# EDAv0_1.net
KiCad netlist of a schematic drawn in EasyEDA Pro
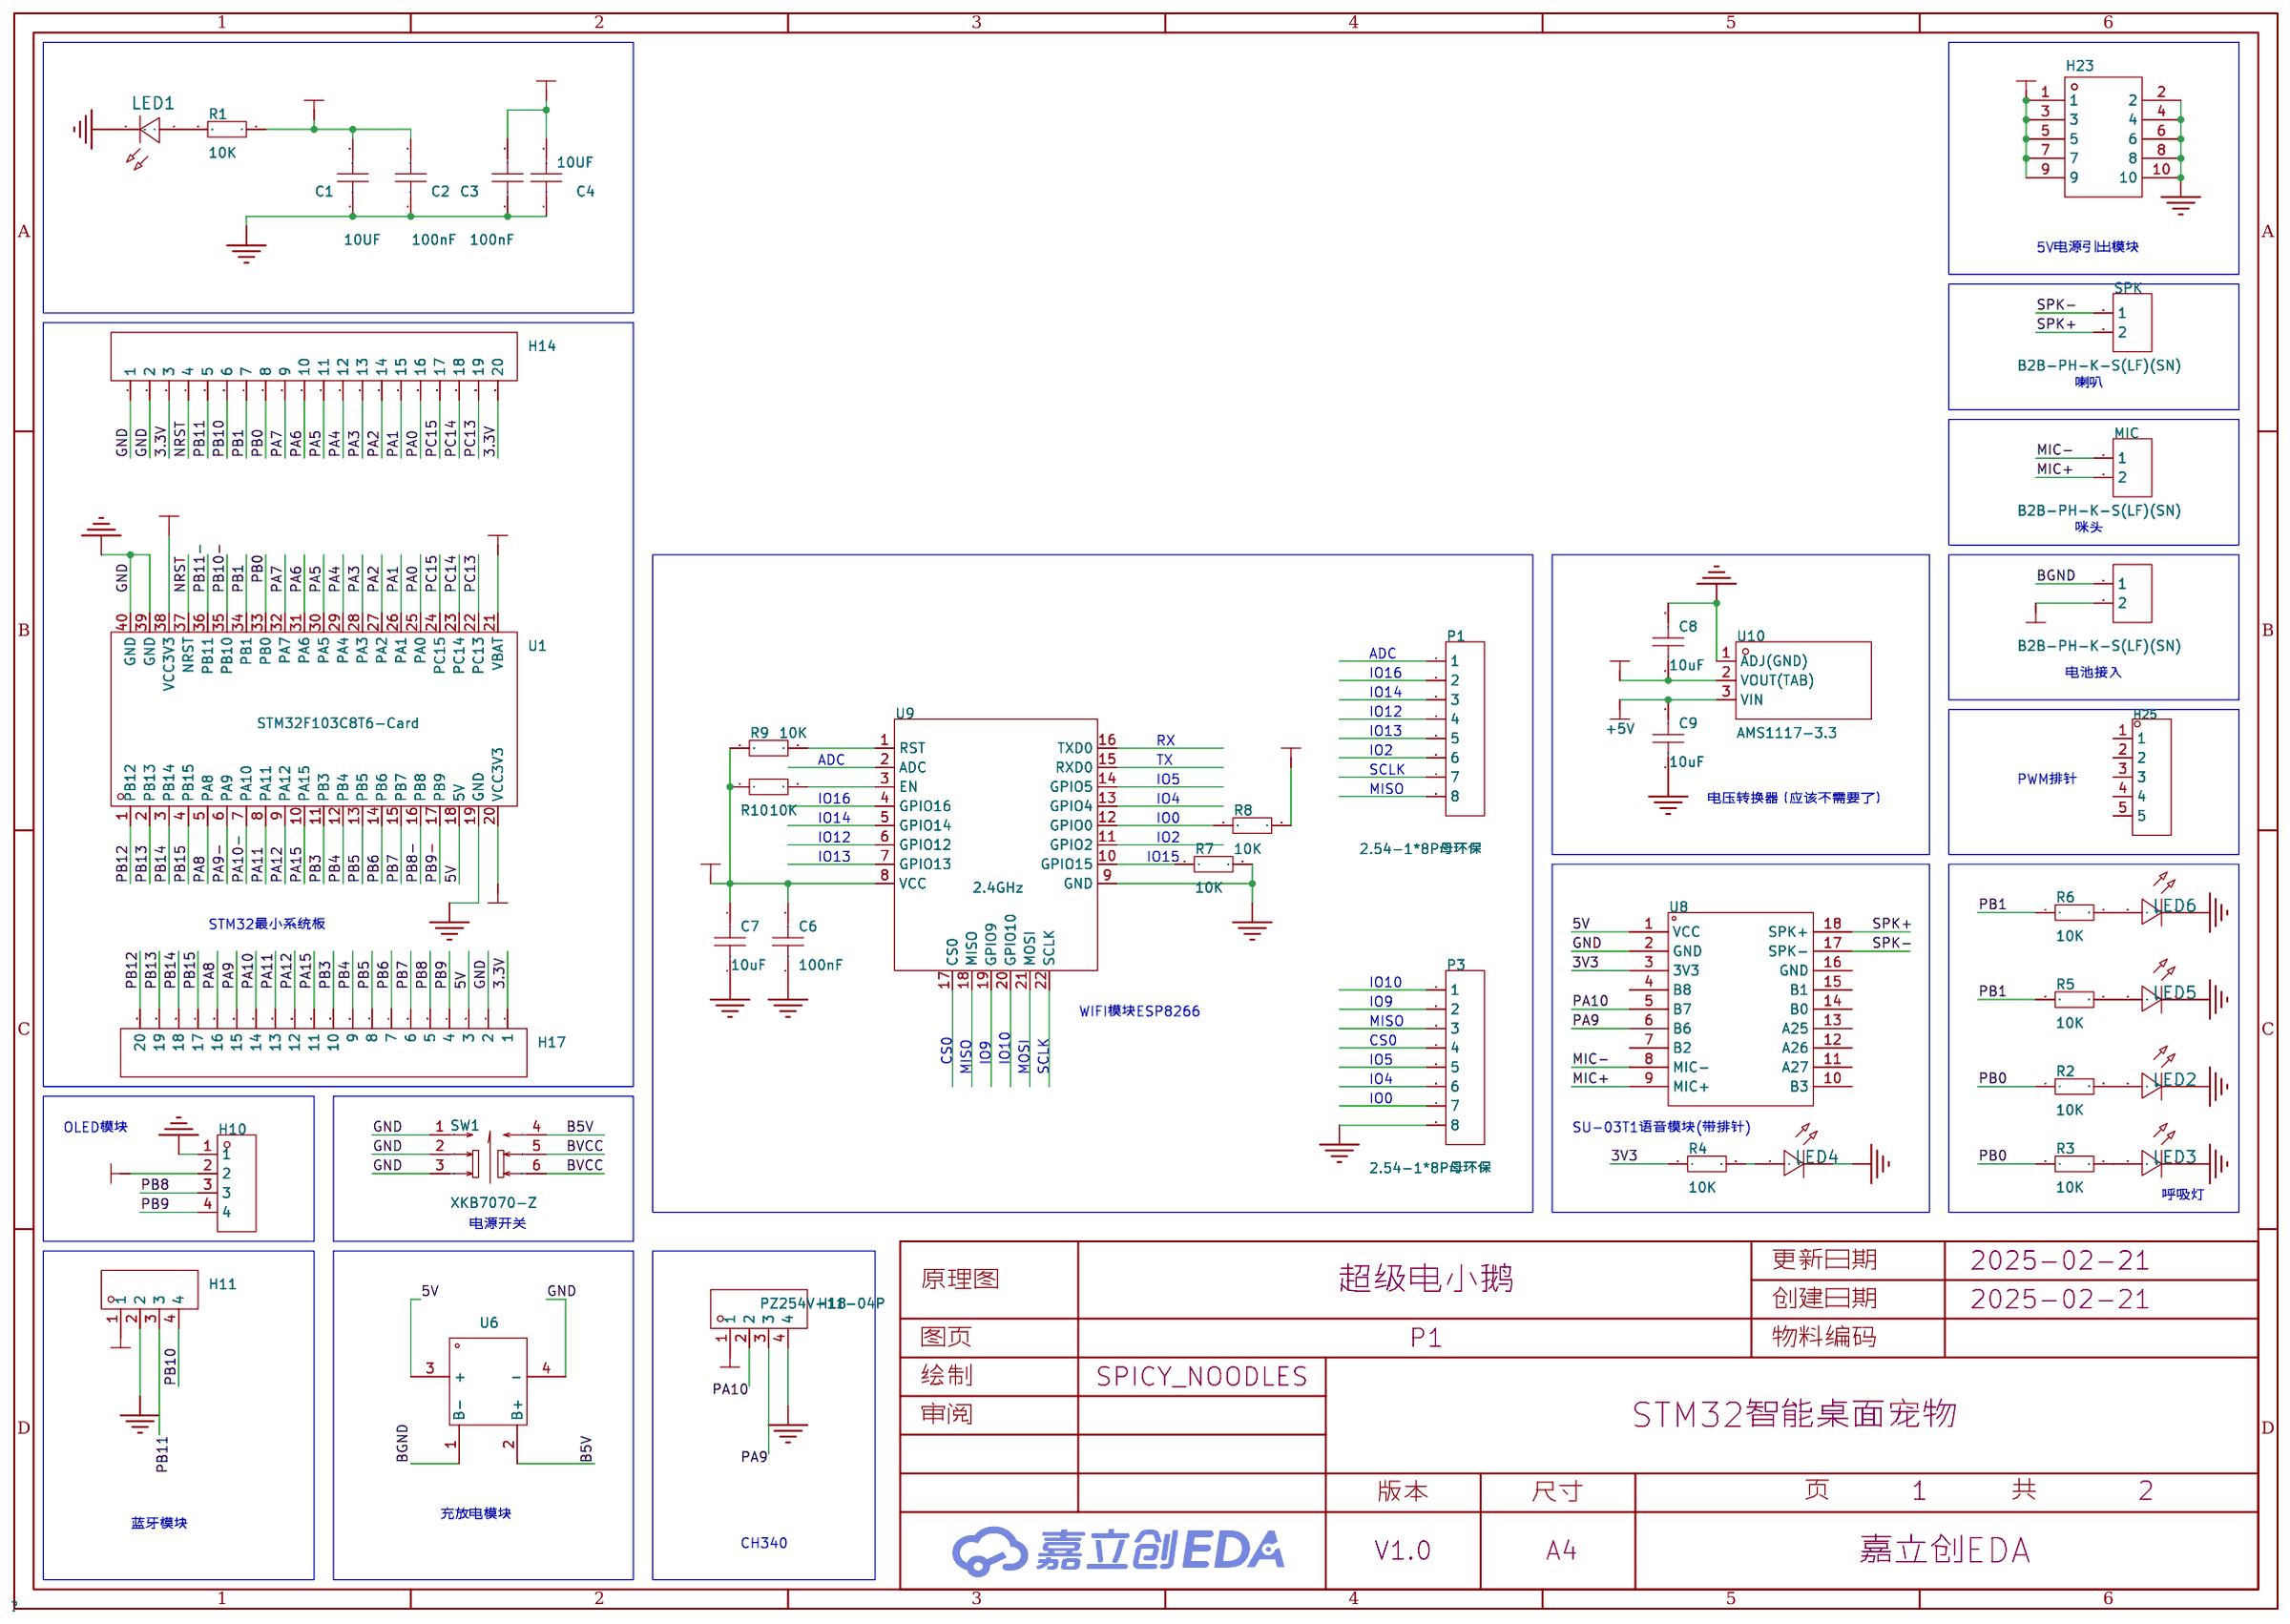
[diagram p0: schematic sheet]

(export (version "E")
  (design (tool "Eeschema 10.0.6"))
  (components
    (comp (ref "Battery")
      (value "B2B-PH-K-S(LF)(SN)")
      (footprint "easyedapro:HDR-TH_2P-P2.54-V-F")
      (fields (field (name "Manufacturer") "JST"))
      (libsource (lib "easyedapro") (part "Header-Female-2.54_1x2"))
    )
    (comp (ref "C1")
      (value "10UF")
      (footprint "easyedapro:C0805")
      (libsource (lib "easyedapro") (part "CapAcitance"))
    )
    (comp (ref "C2")
      (value "100nF")
      (footprint "easyedapro:C0805")
      (libsource (lib "easyedapro") (part "CapAcitance"))
    )
    (comp (ref "C3")
      (value "100nF")
      (footprint "easyedapro:C0805")
      (libsource (lib "easyedapro") (part "CapAcitance"))
    )
    (comp (ref "C4")
      (value "10UF")
      (footprint "easyedapro:C0805")
      (libsource (lib "easyedapro") (part "CapAcitance"))
    )
    (comp (ref "C6")
      (value "100nF")
      (footprint "easyedapro:C0805")
      (libsource (lib "easyedapro") (part "CapAcitance"))
    )
    (comp (ref "C7")
      (value "10uF")
      (footprint "easyedapro:C0603")
      (description "容值:10uF;精度:±10%;额定电压:10V;材质(温度系数):X5R;")
      (fields
        (field (name "Manufacturer Part") "CGA0603X5R106K100JT")
        (field (name "Manufacturer") "HRE(芯声)")
      )
      (libsource (lib "easyedapro") (part "CGA0603X5R106K100JT"))
    )
    (comp (ref "C8")
      (value "10uF")
      (footprint "easyedapro:C0603")
      (description "容值:10uF;精度:±10%;额定电压:10V;材质(温度系数):X5R;")
      (fields
        (field (name "Manufacturer Part") "CGA0603X5R106K100JT")
        (field (name "Manufacturer") "HRE(芯声)")
      )
      (libsource (lib "easyedapro") (part "CGA0603X5R106K100JT"))
    )
    (comp (ref "C9")
      (value "10uF")
      (footprint "easyedapro:C0603")
      (description "容值:10uF;精度:±10%;额定电压:10V;材质(温度系数):X5R;")
      (fields
        (field (name "Manufacturer Part") "CGA0603X5R106K100JT")
        (field (name "Manufacturer") "HRE(芯声)")
      )
      (libsource (lib "easyedapro") (part "CGA0603X5R106K100JT"))
    )
    (comp (ref "H10")
      (value "~")
      (footprint "easyedapro:HDR-TH_4P-P2.54-V-F")
      (libsource (lib "easyedapro") (part "2.54-1*4P母"))
    )
    (comp (ref "H11")
      (value "~")
      (footprint "easyedapro:HDR-TH_4P-P2.54-V-F")
      (libsource (lib "easyedapro") (part "2.54-1*4P母"))
    )
    (comp (ref "H14")
      (value "~")
      (footprint "easyedapro:HDR-TH_20P-P2.54-V-F")
      (libsource (lib "easyedapro") (part "HDR-F_2.54_1x20P"))
    )
    (comp (ref "H17")
      (value "~")
      (footprint "easyedapro:HDR-TH_20P-P2.54-V-F")
      (libsource (lib "easyedapro") (part "HDR-F_2.54_1x20P"))
    )
    (comp (ref "H18")
      (value "PZ254V-11-04P")
      (footprint "easyedapro:HDR-TH_4P-P2.54-V-F")
      (fields (field (name "Manufacturer") "XFCN(兴飞)"))
      (libsource (lib "easyedapro") (part "2.54-1*4P母"))
    )
    (comp (ref "H23")
      (value "~")
      (footprint "easyedapro:HDR-TH_10P-P2.54-V-M-R2-C5-S2.54")
      (libsource (lib "easyedapro") (part "HDR-M-2.54_2x5"))
    )
    (comp (ref "H25")
      (value "~")
      (footprint "easyedapro:HDR-TH_5P-P2.54-V-M")
      (libsource (lib "easyedapro") (part "MTP125-1105S1"))
    )
    (comp (ref "LED1")
      (value "~")
      (footprint "easyedapro:LED_0805")
      (libsource (lib "easyedapro") (part "LED_R"))
    )
    (comp (ref "LED2")
      (value "~")
      (footprint "easyedapro:LED_0805")
      (libsource (lib "easyedapro") (part "LED_R"))
    )
    (comp (ref "LED3")
      (value "~")
      (footprint "easyedapro:LED_0805")
      (libsource (lib "easyedapro") (part "LED_R"))
    )
    (comp (ref "LED4")
      (value "~")
      (footprint "easyedapro:LED_0805")
      (libsource (lib "easyedapro") (part "LED_R"))
    )
    (comp (ref "LED5")
      (value "~")
      (footprint "easyedapro:LED_0805")
      (libsource (lib "easyedapro") (part "LED_R"))
    )
    (comp (ref "LED6")
      (value "~")
      (footprint "easyedapro:LED_0805")
      (libsource (lib "easyedapro") (part "LED_R"))
    )
    (comp (ref "MIC")
      (value "B2B-PH-K-S(LF)(SN)")
      (footprint "easyedapro:HDR-TH_2P-P2.54-V-F")
      (fields (field (name "Manufacturer") "JST"))
      (libsource (lib "easyedapro") (part "Header-Female-2.54_1x2"))
    )
    (comp (ref "P1")
      (value "2.54-1*8P母环保")
      (footprint "easyedapro:HDR-TH_8P-P2.54-V-F-1")
      (description "插孔结构:1x8P;间距:2.54mm;行距:-;安装类型:直插;排数:单排;总孔位数:8P;塑高:-;触头材质:-;触头镀层:-;")
      (fields (field (name "Manufacturer") "BOOMELE(博穆精密)"))
      (libsource (lib "easyedapro") (part "Header-Female-2.54_1x8"))
    )
    (comp (ref "P3")
      (value "2.54-1*8P母环保")
      (footprint "easyedapro:HDR-TH_8P-P2.54-V-F-1")
      (description "插孔结构:1x8P;间距:2.54mm;行距:-;安装类型:直插;排数:单排;总孔位数:8P;塑高:-;触头材质:-;触头镀层:-;")
      (fields (field (name "Manufacturer") "BOOMELE(博穆精密)"))
      (libsource (lib "easyedapro") (part "Header-Female-2.54_1x8"))
    )
    (comp (ref "R1") (value "10K") (footprint "easyedapro:R0805") (libsource (lib "easyedapro") (part "电阻")))
    (comp (ref "R2") (value "10K") (footprint "easyedapro:R0805") (libsource (lib "easyedapro") (part "电阻")))
    (comp (ref "R3") (value "10K") (footprint "easyedapro:R0805") (libsource (lib "easyedapro") (part "电阻")))
    (comp (ref "R4") (value "10K") (footprint "easyedapro:R0805") (libsource (lib "easyedapro") (part "电阻")))
    (comp (ref "R5") (value "10K") (footprint "easyedapro:R0805") (libsource (lib "easyedapro") (part "电阻")))
    (comp (ref "R6") (value "10K") (footprint "easyedapro:R0805") (libsource (lib "easyedapro") (part "电阻")))
    (comp (ref "R7") (value "10K") (footprint "easyedapro:R0805") (libsource (lib "easyedapro") (part "电阻")))
    (comp (ref "R8") (value "10K") (footprint "easyedapro:R0805") (libsource (lib "easyedapro") (part "电阻")))
    (comp (ref "R9") (value "10K") (footprint "easyedapro:R0805") (libsource (lib "easyedapro") (part "电阻")))
    (comp (ref "R10") (value "10K") (footprint "easyedapro:R0805") (libsource (lib "easyedapro") (part "电阻")))
    (comp (ref "SPK")
      (value "B2B-PH-K-S(LF)(SN)")
      (footprint "easyedapro:HDR-TH_2P-P2.54-V-F")
      (fields (field (name "Manufacturer") "JST"))
      (libsource (lib "easyedapro") (part "Header-Female-2.54_1x2"))
    )
    (comp (ref "SW1")
      (value "XKB7070-Z")
      (footprint "easyedapro:SW-TH_6P-L7.0-W7.0-P2.00")
      (description "自锁/无锁:自锁;安装方式:直插;触点电流:100mA;额定电压 (AC):250V;额定电压 (DC):30V;带灯:不带;作用力:160gf;机械寿命:10万次;")
      (fields (field (name "Manufacturer") "XKB Connectivity(中国星坤)"))
      (libsource (lib "easyedapro") (part "XKB7070-Z"))
    )
    (comp (ref "U1")
      (value "STM32F103C8T6-Card")
      (footprint "easyedapro:CONN-TH_L53.3-W22.9_STM32F103C8T6-CARD")
      (libsource (lib "easyedapro") (part "STM32F103C8T6-CARD"))
    )
    (comp (ref "U6") (value "~") (libsource (lib "easyedapro") (part "5V充放电模块")))
    (comp (ref "U8")
      (value "~")
      (footprint "easyedapro:SU-03T带排针")
      (libsource (lib "easyedapro") (part "SU-03T带排针"))
    )
    (comp (ref "U9")
      (value "2.4GHz")
      (footprint "easyedapro:WIFIM-SMD_ESP-12F-ESP8266MOD")
      (description "核心处理器:ESP8266芯片;频率:2.4GHz;天线形式:板载PCB天线;发射功率:16dBm;接收灵敏度:-90dBm;")
      (fields
        (field (name "Manufacturer Part") "ESP-12F(ESP8266MOD)")
        (field (name "Manufacturer") "Ai-Thinker(安信可)")
      )
      (libsource (lib "easyedapro") (part "ESP-12F(ESP8266MOD)"))
    )
    (comp (ref "U10")
      (value "AMS1117-3.3")
      (footprint "easyedapro:SOT-89_L4.5-W2.5-P1.50-LS4.2-BR")
      (description "输出类型:固定;工作电压:18V;输出电压:3.3V;输出电流:1A;电源纹波抑制比(PSRR):60dB@(120Hz);输出极性:正极;")
      (fields (field (name "Manufacturer") "UMW(友台半导体)"))
      (libsource (lib "easyedapro") (part "AMS1117-3.3_C347256"))
    )
  )
  (nets
    (net (code "1") (name "+5V") (class "Default")
      (node (ref "C9") (pin "2") (pinfunction "2_2") (pintype "unspecified"))
      (node (ref "U10") (pin "3") (pinfunction "VIN_3") (pintype "unspecified"))
    )
    (net (code "2") (name "/3V3") (class "Default")
      (node (ref "R4") (pin "1") (pinfunction "1_1") (pintype "input"))
      (node (ref "U8") (pin "3") (pinfunction "3V3_3") (pintype "input"))
    )
    (net (code "3") (name "/B5V") (class "Default")
      (node (ref "SW1") (pin "4") (pinfunction "4_4") (pintype "unspecified"))
      (node (ref "U6") (pin "2") (pinfunction "B+_2") (pintype "input"))
    )
    (net (code "4") (name "/BGND") (class "Default")
      (node (ref "Battery") (pin "1") (pinfunction "1_1") (pintype "input"))
      (node (ref "U6") (pin "1") (pinfunction "B-_1") (pintype "input"))
    )
    (net (code "5") (name "/MIC+") (class "Default")
      (node (ref "MIC") (pin "2") (pinfunction "2_2") (pintype "input"))
      (node (ref "U8") (pin "9") (pinfunction "MIC+_9") (pintype "input"))
    )
    (net (code "6") (name "/MIC-") (class "Default")
      (node (ref "MIC") (pin "1") (pinfunction "1_1") (pintype "input"))
      (node (ref "U8") (pin "8") (pinfunction "MIC-_8") (pintype "input"))
    )
    (net (code "7") (name "/NRST") (class "Default")
      (node (ref "H14") (pin "4") (pinfunction "4_4") (pintype "input"))
      (node (ref "U1") (pin "37") (pinfunction "NRST_37") (pintype "unspecified"))
    )
    (net (code "8") (name "/PA0") (class "Default")
      (node (ref "H14") (pin "16") (pinfunction "16_16") (pintype "input"))
      (node (ref "U1") (pin "25") (pinfunction "PA0_25") (pintype "unspecified"))
    )
    (net (code "9") (name "/PA1") (class "Default")
      (node (ref "H14") (pin "15") (pinfunction "15_15") (pintype "input"))
      (node (ref "U1") (pin "26") (pinfunction "PA1_26") (pintype "unspecified"))
    )
    (net (code "10") (name "/PA2") (class "Default")
      (node (ref "H14") (pin "14") (pinfunction "14_14") (pintype "input"))
      (node (ref "U1") (pin "27") (pinfunction "PA2_27") (pintype "unspecified"))
    )
    (net (code "11") (name "/PA3") (class "Default")
      (node (ref "H14") (pin "13") (pinfunction "13_13") (pintype "input"))
      (node (ref "U1") (pin "28") (pinfunction "PA3_28") (pintype "unspecified"))
    )
    (net (code "12") (name "/PA4") (class "Default")
      (node (ref "H14") (pin "12") (pinfunction "12_12") (pintype "input"))
      (node (ref "U1") (pin "29") (pinfunction "PA4_29") (pintype "unspecified"))
    )
    (net (code "13") (name "/PA5") (class "Default")
      (node (ref "H14") (pin "11") (pinfunction "11_11") (pintype "input"))
      (node (ref "U1") (pin "30") (pinfunction "PA5_30") (pintype "unspecified"))
    )
    (net (code "14") (name "/PA6") (class "Default")
      (node (ref "H14") (pin "10") (pinfunction "10_10") (pintype "input"))
      (node (ref "U1") (pin "31") (pinfunction "PA6_31") (pintype "unspecified"))
    )
    (net (code "15") (name "/PA7") (class "Default")
      (node (ref "H14") (pin "9") (pinfunction "9_9") (pintype "input"))
      (node (ref "U1") (pin "32") (pinfunction "PA7_32") (pintype "unspecified"))
    )
    (net (code "16") (name "/PA8") (class "Default")
      (node (ref "H17") (pin "16") (pinfunction "16_16") (pintype "input"))
      (node (ref "U1") (pin "5") (pinfunction "PA8_5") (pintype "unspecified"))
    )
    (net (code "17") (name "/PA9") (class "Default")
      (node (ref "H17") (pin "15") (pinfunction "15_15") (pintype "input"))
      (node (ref "H18") (pin "3") (pinfunction "3_3") (pintype "unspecified"))
      (node (ref "U8") (pin "6") (pinfunction "B6_6") (pintype "input"))
    )
    (net (code "18") (name "/PA9-") (class "Default")
      (node (ref "U1") (pin "6") (pinfunction "PA9_6") (pintype "unspecified"))
    )
    (net (code "19") (name "/PA10") (class "Default")
      (node (ref "H17") (pin "14") (pinfunction "14_14") (pintype "input"))
      (node (ref "H18") (pin "2") (pinfunction "2_2") (pintype "unspecified"))
      (node (ref "U8") (pin "5") (pinfunction "B7_5") (pintype "input"))
    )
    (net (code "20") (name "/PA10-") (class "Default")
      (node (ref "U1") (pin "7") (pinfunction "PA10_7") (pintype "unspecified"))
    )
    (net (code "21") (name "/PA11") (class "Default")
      (node (ref "H17") (pin "13") (pinfunction "13_13") (pintype "input"))
      (node (ref "U1") (pin "8") (pinfunction "PA11_8") (pintype "unspecified"))
    )
    (net (code "22") (name "/PA12") (class "Default")
      (node (ref "H17") (pin "12") (pinfunction "12_12") (pintype "input"))
      (node (ref "U1") (pin "9") (pinfunction "PA12_9") (pintype "unspecified"))
    )
    (net (code "23") (name "/PA15") (class "Default")
      (node (ref "H17") (pin "11") (pinfunction "11_11") (pintype "input"))
      (node (ref "U1") (pin "10") (pinfunction "PA15_10") (pintype "unspecified"))
    )
    (net (code "24") (name "/PB0") (class "Default")
      (node (ref "H14") (pin "8") (pinfunction "8_8") (pintype "input"))
      (node (ref "R2") (pin "1") (pinfunction "1_1") (pintype "input"))
      (node (ref "R3") (pin "1") (pinfunction "1_1") (pintype "input"))
      (node (ref "U1") (pin "33") (pinfunction "PB0_33") (pintype "unspecified"))
    )
    (net (code "25") (name "/PB1") (class "Default")
      (node (ref "H14") (pin "7") (pinfunction "7_7") (pintype "input"))
      (node (ref "R5") (pin "1") (pinfunction "1_1") (pintype "input"))
      (node (ref "R6") (pin "1") (pinfunction "1_1") (pintype "input"))
      (node (ref "U1") (pin "34") (pinfunction "PB1_34") (pintype "unspecified"))
    )
    (net (code "26") (name "/PB3") (class "Default")
      (node (ref "H17") (pin "10") (pinfunction "10_10") (pintype "input"))
      (node (ref "U1") (pin "11") (pinfunction "PB3_11") (pintype "unspecified"))
    )
    (net (code "27") (name "/PB4") (class "Default")
      (node (ref "H17") (pin "9") (pinfunction "9_9") (pintype "input"))
      (node (ref "U1") (pin "12") (pinfunction "PB4_12") (pintype "unspecified"))
    )
    (net (code "28") (name "/PB5") (class "Default")
      (node (ref "H17") (pin "8") (pinfunction "8_8") (pintype "input"))
      (node (ref "U1") (pin "13") (pinfunction "PB5_13") (pintype "unspecified"))
    )
    (net (code "29") (name "/PB6") (class "Default")
      (node (ref "H17") (pin "7") (pinfunction "7_7") (pintype "input"))
      (node (ref "U1") (pin "14") (pinfunction "PB6_14") (pintype "unspecified"))
    )
    (net (code "30") (name "/PB7") (class "Default")
      (node (ref "H17") (pin "6") (pinfunction "6_6") (pintype "input"))
      (node (ref "U1") (pin "15") (pinfunction "PB7_15") (pintype "unspecified"))
    )
    (net (code "31") (name "/PB8") (class "Default")
      (node (ref "H10") (pin "3") (pinfunction "3_3") (pintype "unspecified"))
      (node (ref "H17") (pin "5") (pinfunction "5_5") (pintype "input"))
    )
    (net (code "32") (name "/PB8-") (class "Default")
      (node (ref "U1") (pin "16") (pinfunction "PB8_16") (pintype "unspecified"))
    )
    (net (code "33") (name "/PB9") (class "Default")
      (node (ref "H10") (pin "4") (pinfunction "4_4") (pintype "unspecified"))
      (node (ref "H17") (pin "4") (pinfunction "4_4") (pintype "input"))
    )
    (net (code "34") (name "/PB9-") (class "Default")
      (node (ref "U1") (pin "17") (pinfunction "PB9_17") (pintype "unspecified"))
    )
    (net (code "35") (name "/PB10") (class "Default")
      (node (ref "H11") (pin "4") (pinfunction "4_4") (pintype "unspecified"))
      (node (ref "H14") (pin "6") (pinfunction "6_6") (pintype "input"))
    )
    (net (code "36") (name "/PB10-") (class "Default")
      (node (ref "U1") (pin "35") (pinfunction "PB10_35") (pintype "unspecified"))
    )
    (net (code "37") (name "/PB11") (class "Default")
      (node (ref "H11") (pin "3") (pinfunction "3_3") (pintype "unspecified"))
      (node (ref "H14") (pin "5") (pinfunction "5_5") (pintype "input"))
    )
    (net (code "38") (name "/PB11-") (class "Default")
      (node (ref "U1") (pin "36") (pinfunction "PB11_36") (pintype "unspecified"))
    )
    (net (code "39") (name "/PB12") (class "Default")
      (node (ref "H17") (pin "20") (pinfunction "20_20") (pintype "input"))
      (node (ref "U1") (pin "1") (pinfunction "PB12_1") (pintype "unspecified"))
    )
    (net (code "40") (name "/PB13") (class "Default")
      (node (ref "H17") (pin "19") (pinfunction "19_19") (pintype "input"))
      (node (ref "U1") (pin "2") (pinfunction "PB13_2") (pintype "unspecified"))
    )
    (net (code "41") (name "/PB14") (class "Default")
      (node (ref "H17") (pin "18") (pinfunction "18_18") (pintype "input"))
      (node (ref "U1") (pin "3") (pinfunction "PB14_3") (pintype "unspecified"))
    )
    (net (code "42") (name "/PB15") (class "Default")
      (node (ref "H17") (pin "17") (pinfunction "17_17") (pintype "input"))
      (node (ref "U1") (pin "4") (pinfunction "PB15_4") (pintype "unspecified"))
    )
    (net (code "43") (name "/PC13") (class "Default")
      (node (ref "H14") (pin "19") (pinfunction "19_19") (pintype "input"))
      (node (ref "U1") (pin "22") (pinfunction "PC13_22") (pintype "unspecified"))
    )
    (net (code "44") (name "/PC14") (class "Default")
      (node (ref "H14") (pin "18") (pinfunction "18_18") (pintype "input"))
      (node (ref "U1") (pin "23") (pinfunction "PC14_23") (pintype "unspecified"))
    )
    (net (code "45") (name "/PC15") (class "Default")
      (node (ref "H14") (pin "17") (pinfunction "17_17") (pintype "input"))
      (node (ref "U1") (pin "24") (pinfunction "PC15_24") (pintype "unspecified"))
    )
    (net (code "46") (name "/SPK+") (class "Default")
      (node (ref "SPK") (pin "2") (pinfunction "2_2") (pintype "input"))
      (node (ref "U8") (pin "18") (pinfunction "SPK+_18") (pintype "input"))
    )
    (net (code "47") (name "/SPK-") (class "Default")
      (node (ref "SPK") (pin "1") (pinfunction "1_1") (pintype "input"))
      (node (ref "U8") (pin "17") (pinfunction "SPK-_17") (pintype "input"))
    )
    (net (code "48") (name "3.3V") (class "Default")
      (node (ref "C3") (pin "2") (pinfunction "2_2") (pintype "input"))
      (node (ref "C4") (pin "2") (pinfunction "2_2") (pintype "input"))
      (node (ref "C6") (pin "2") (pinfunction "2_2") (pintype "input"))
      (node (ref "C7") (pin "2") (pinfunction "2_2") (pintype "unspecified"))
      (node (ref "C8") (pin "1") (pinfunction "1_1") (pintype "unspecified"))
      (node (ref "H10") (pin "2") (pinfunction "2_2") (pintype "unspecified"))
      (node (ref "H11") (pin "1") (pinfunction "1_1") (pintype "unspecified"))
      (node (ref "H14") (pin "20") (pinfunction "20_20") (pintype "input"))
      (node (ref "H14") (pin "3") (pinfunction "3_3") (pintype "input"))
      (node (ref "H17") (pin "1") (pinfunction "1_1") (pintype "input"))
      (node (ref "R10") (pin "1") (pinfunction "1_1") (pintype "input"))
      (node (ref "R8") (pin "2") (pinfunction "2_2") (pintype "input"))
      (node (ref "R9") (pin "1") (pinfunction "1_1") (pintype "input"))
      (node (ref "U1") (pin "20") (pinfunction "VCC3V3_20") (pintype "unspecified"))
      (node (ref "U1") (pin "21") (pinfunction "VBAT_21") (pintype "unspecified"))
      (node (ref "U1") (pin "38") (pinfunction "VCC3V3_38") (pintype "unspecified"))
      (node (ref "U10") (pin "2") (pinfunction "VOUT(TAB)_2") (pintype "unspecified"))
      (node (ref "U9") (pin "8") (pinfunction "VCC_8") (pintype "unspecified"))
    )
    (net (code "49") (name "5V") (class "Default")
      (node (ref "C1") (pin "2") (pinfunction "2_2") (pintype "input"))
      (node (ref "C2") (pin "2") (pinfunction "2_2") (pintype "input"))
      (node (ref "H17") (pin "3") (pinfunction "3_3") (pintype "input"))
      (node (ref "H18") (pin "1") (pinfunction "1_1") (pintype "unspecified"))
      (node (ref "H23") (pin "1") (pinfunction "1_1") (pintype "input"))
      (node (ref "H23") (pin "3") (pinfunction "3_3") (pintype "input"))
      (node (ref "H23") (pin "5") (pinfunction "5_5") (pintype "input"))
      (node (ref "H23") (pin "7") (pinfunction "7_7") (pintype "input"))
      (node (ref "H23") (pin "9") (pinfunction "9_9") (pintype "input"))
      (node (ref "R1") (pin "1") (pinfunction "1_1") (pintype "input"))
      (node (ref "U1") (pin "18") (pinfunction "5V_18") (pintype "unspecified"))
      (node (ref "U6") (pin "3") (pinfunction "+_3") (pintype "input"))
      (node (ref "U8") (pin "1") (pinfunction "VCC_1") (pintype "input"))
    )
    (net (code "50") (name "BVCC") (class "Default")
      (node (ref "Battery") (pin "2") (pinfunction "2_2") (pintype "input"))
      (node (ref "SW1") (pin "5") (pinfunction "5_5") (pintype "unspecified"))
      (node (ref "SW1") (pin "6") (pinfunction "6_6") (pintype "unspecified"))
    )
    (net (code "51") (name "GND") (class "Default")
      (node (ref "C1") (pin "1") (pinfunction "1_1") (pintype "input"))
      (node (ref "C2") (pin "1") (pinfunction "1_1") (pintype "input"))
      (node (ref "C3") (pin "1") (pinfunction "1_1") (pintype "input"))
      (node (ref "C4") (pin "1") (pinfunction "1_1") (pintype "input"))
      (node (ref "C6") (pin "1") (pinfunction "1_1") (pintype "input"))
      (node (ref "C7") (pin "1") (pinfunction "1_1") (pintype "unspecified"))
      (node (ref "C8") (pin "2") (pinfunction "2_2") (pintype "unspecified"))
      (node (ref "C9") (pin "1") (pinfunction "1_1") (pintype "unspecified"))
      (node (ref "H10") (pin "1") (pinfunction "1_1") (pintype "unspecified"))
      (node (ref "H11") (pin "2") (pinfunction "2_2") (pintype "unspecified"))
      (node (ref "H14") (pin "1") (pinfunction "1_1") (pintype "input"))
      (node (ref "H14") (pin "2") (pinfunction "2_2") (pintype "input"))
      (node (ref "H17") (pin "2") (pinfunction "2_2") (pintype "input"))
      (node (ref "H18") (pin "4") (pinfunction "4_4") (pintype "unspecified"))
      (node (ref "H23") (pin "10") (pinfunction "10_10") (pintype "input"))
      (node (ref "H23") (pin "2") (pinfunction "2_2") (pintype "input"))
      (node (ref "H23") (pin "4") (pinfunction "4_4") (pintype "input"))
      (node (ref "H23") (pin "6") (pinfunction "6_6") (pintype "input"))
      (node (ref "H23") (pin "8") (pinfunction "8_8") (pintype "input"))
      (node (ref "LED1") (pin "1") (pinfunction "C_1") (pintype "input"))
      (node (ref "LED2") (pin "1") (pinfunction "C_1") (pintype "input"))
      (node (ref "LED3") (pin "1") (pinfunction "C_1") (pintype "input"))
      (node (ref "LED4") (pin "1") (pinfunction "C_1") (pintype "input"))
      (node (ref "LED5") (pin "1") (pinfunction "C_1") (pintype "input"))
      (node (ref "LED6") (pin "1") (pinfunction "C_1") (pintype "input"))
      (node (ref "P3") (pin "8") (pinfunction "8_8") (pintype "input"))
      (node (ref "R7") (pin "2") (pinfunction "2_2") (pintype "input"))
      (node (ref "SW1") (pin "1") (pinfunction "1_1") (pintype "unspecified"))
      (node (ref "SW1") (pin "2") (pinfunction "2_2") (pintype "unspecified"))
      (node (ref "SW1") (pin "3") (pinfunction "3_3") (pintype "unspecified"))
      (node (ref "U1") (pin "19") (pinfunction "GND_19") (pintype "unspecified"))
      (node (ref "U1") (pin "39") (pinfunction "GND_39") (pintype "unspecified"))
      (node (ref "U1") (pin "40") (pinfunction "GND_40") (pintype "unspecified"))
      (node (ref "U10") (pin "1") (pinfunction "ADJ(GND)_1") (pintype "unspecified"))
      (node (ref "U6") (pin "4") (pinfunction "-_4") (pintype "input"))
      (node (ref "U8") (pin "2") (pinfunction "GND_2") (pintype "input"))
      (node (ref "U9") (pin "9") (pinfunction "GND_9") (pintype "unspecified"))
    )
    (net (code "52") (name "Net-(LED1-A)") (class "Default")
      (node (ref "LED1") (pin "2") (pinfunction "A_2") (pintype "input"))
      (node (ref "R1") (pin "2") (pinfunction "2_2") (pintype "input"))
    )
    (net (code "53") (name "Net-(LED2-A)") (class "Default")
      (node (ref "LED2") (pin "2") (pinfunction "A_2") (pintype "input"))
      (node (ref "R2") (pin "2") (pinfunction "2_2") (pintype "input"))
    )
    (net (code "54") (name "Net-(LED3-A)") (class "Default")
      (node (ref "LED3") (pin "2") (pinfunction "A_2") (pintype "input"))
      (node (ref "R3") (pin "2") (pinfunction "2_2") (pintype "input"))
    )
    (net (code "55") (name "Net-(LED4-A)") (class "Default")
      (node (ref "LED4") (pin "2") (pinfunction "A_2") (pintype "input"))
      (node (ref "R4") (pin "2") (pinfunction "2_2") (pintype "input"))
    )
    (net (code "56") (name "Net-(LED5-A)") (class "Default")
      (node (ref "LED5") (pin "2") (pinfunction "A_2") (pintype "input"))
      (node (ref "R5") (pin "2") (pinfunction "2_2") (pintype "input"))
    )
    (net (code "57") (name "Net-(LED6-A)") (class "Default")
      (node (ref "LED6") (pin "2") (pinfunction "A_2") (pintype "input"))
      (node (ref "R6") (pin "2") (pinfunction "2_2") (pintype "input"))
    )
    (net (code "58") (name "Net-(U9-EN)") (class "Default")
      (node (ref "R10") (pin "2") (pinfunction "2_2") (pintype "input"))
      (node (ref "U9") (pin "3") (pinfunction "EN_3") (pintype "unspecified"))
    )
    (net (code "59") (name "Net-(U9-GPIO0)") (class "Default")
      (node (ref "R8") (pin "1") (pinfunction "1_1") (pintype "input"))
      (node (ref "U9") (pin "12") (pinfunction "GPIO0_12") (pintype "unspecified"))
    )
    (net (code "60") (name "Net-(U9-GPIO15)") (class "Default")
      (node (ref "R7") (pin "1") (pinfunction "1_1") (pintype "input"))
      (node (ref "U9") (pin "10") (pinfunction "GPIO15_10") (pintype "unspecified"))
    )
    (net (code "61") (name "Net-(U9-RST)") (class "Default")
      (node (ref "R9") (pin "2") (pinfunction "2_2") (pintype "input"))
      (node (ref "U9") (pin "1") (pinfunction "RST_1") (pintype "unspecified"))
    )
    (net (code "62") (name "unconnected-(H25-Pad1)") (class "Default")
      (node (ref "H25") (pin "1") (pinfunction "1_1") (pintype "input"))
    )
    (net (code "63") (name "unconnected-(H25-Pad2)") (class "Default")
      (node (ref "H25") (pin "2") (pinfunction "2_2") (pintype "input"))
    )
    (net (code "64") (name "unconnected-(H25-Pad3)") (class "Default")
      (node (ref "H25") (pin "3") (pinfunction "3_3") (pintype "input"))
    )
    (net (code "65") (name "unconnected-(H25-Pad4)") (class "Default")
      (node (ref "H25") (pin "4") (pinfunction "4_4") (pintype "input"))
    )
    (net (code "66") (name "unconnected-(H25-Pad5)") (class "Default")
      (node (ref "H25") (pin "5") (pinfunction "5_5") (pintype "input"))
    )
    (net (code "67") (name "unconnected-(P1-Pad1)") (class "Default")
      (node (ref "P1") (pin "1") (pinfunction "1_1") (pintype "input"))
    )
    (net (code "68") (name "unconnected-(P1-Pad2)") (class "Default")
      (node (ref "P1") (pin "2") (pinfunction "2_2") (pintype "input"))
    )
    (net (code "69") (name "unconnected-(P1-Pad3)") (class "Default")
      (node (ref "P1") (pin "3") (pinfunction "3_3") (pintype "input"))
    )
    (net (code "70") (name "unconnected-(P1-Pad4)") (class "Default")
      (node (ref "P1") (pin "4") (pinfunction "4_4") (pintype "input"))
    )
    (net (code "71") (name "unconnected-(P1-Pad5)") (class "Default")
      (node (ref "P1") (pin "5") (pinfunction "5_5") (pintype "input"))
    )
    (net (code "72") (name "unconnected-(P1-Pad6)") (class "Default")
      (node (ref "P1") (pin "6") (pinfunction "6_6") (pintype "input"))
    )
    (net (code "73") (name "unconnected-(P1-Pad7)") (class "Default")
      (node (ref "P1") (pin "7") (pinfunction "7_7") (pintype "input"))
    )
    (net (code "74") (name "unconnected-(P1-Pad8)") (class "Default")
      (node (ref "P1") (pin "8") (pinfunction "8_8") (pintype "input"))
    )
    (net (code "75") (name "unconnected-(P3-Pad1)") (class "Default")
      (node (ref "P3") (pin "1") (pinfunction "1_1") (pintype "input"))
    )
    (net (code "76") (name "unconnected-(P3-Pad2)") (class "Default")
      (node (ref "P3") (pin "2") (pinfunction "2_2") (pintype "input"))
    )
    (net (code "77") (name "unconnected-(P3-Pad3)") (class "Default")
      (node (ref "P3") (pin "3") (pinfunction "3_3") (pintype "input"))
    )
    (net (code "78") (name "unconnected-(P3-Pad4)") (class "Default")
      (node (ref "P3") (pin "4") (pinfunction "4_4") (pintype "input"))
    )
    (net (code "79") (name "unconnected-(P3-Pad5)") (class "Default")
      (node (ref "P3") (pin "5") (pinfunction "5_5") (pintype "input"))
    )
    (net (code "80") (name "unconnected-(P3-Pad6)") (class "Default")
      (node (ref "P3") (pin "6") (pinfunction "6_6") (pintype "input"))
    )
    (net (code "81") (name "unconnected-(P3-Pad7)") (class "Default")
      (node (ref "P3") (pin "7") (pinfunction "7_7") (pintype "input"))
    )
    (net (code "82") (name "unconnected-(U8-A25-Pad13)") (class "Default")
      (node (ref "U8") (pin "13") (pinfunction "A25_13") (pintype "input"))
    )
    (net (code "83") (name "unconnected-(U8-A26-Pad12)") (class "Default")
      (node (ref "U8") (pin "12") (pinfunction "A26_12") (pintype "input"))
    )
    (net (code "84") (name "unconnected-(U8-A27-Pad11)") (class "Default")
      (node (ref "U8") (pin "11") (pinfunction "A27_11") (pintype "input"))
    )
    (net (code "85") (name "unconnected-(U8-B0-Pad14)") (class "Default")
      (node (ref "U8") (pin "14") (pinfunction "B0_14") (pintype "input"))
    )
    (net (code "86") (name "unconnected-(U8-B1-Pad15)") (class "Default")
      (node (ref "U8") (pin "15") (pinfunction "B1_15") (pintype "input"))
    )
    (net (code "87") (name "unconnected-(U8-B2-Pad7)") (class "Default")
      (node (ref "U8") (pin "7") (pinfunction "B2_7") (pintype "input"))
    )
    (net (code "88") (name "unconnected-(U8-B3-Pad10)") (class "Default")
      (node (ref "U8") (pin "10") (pinfunction "B3_10") (pintype "input"))
    )
    (net (code "89") (name "unconnected-(U8-B8-Pad4)") (class "Default")
      (node (ref "U8") (pin "4") (pinfunction "B8_4") (pintype "input"))
    )
    (net (code "90") (name "unconnected-(U8-GND-Pad16)") (class "Default")
      (node (ref "U8") (pin "16") (pinfunction "GND_16") (pintype "input"))
    )
    (net (code "91") (name "unconnected-(U9-ADC-Pad2)") (class "Default")
      (node (ref "U9") (pin "2") (pinfunction "ADC_2") (pintype "unspecified"))
    )
    (net (code "92") (name "unconnected-(U9-CS0-Pad17)") (class "Default")
      (node (ref "U9") (pin "17") (pinfunction "CS0_17") (pintype "unspecified"))
    )
    (net (code "93") (name "unconnected-(U9-GPIO2-Pad11)") (class "Default")
      (node (ref "U9") (pin "11") (pinfunction "GPIO2_11") (pintype "unspecified"))
    )
    (net (code "94") (name "unconnected-(U9-GPIO4-Pad13)") (class "Default")
      (node (ref "U9") (pin "13") (pinfunction "GPIO4_13") (pintype "unspecified"))
    )
    (net (code "95") (name "unconnected-(U9-GPIO5-Pad14)") (class "Default")
      (node (ref "U9") (pin "14") (pinfunction "GPIO5_14") (pintype "unspecified"))
    )
    (net (code "96") (name "unconnected-(U9-GPIO9-Pad19)") (class "Default")
      (node (ref "U9") (pin "19") (pinfunction "GPIO9_19") (pintype "unspecified"))
    )
    (net (code "97") (name "unconnected-(U9-GPIO10-Pad20)") (class "Default")
      (node (ref "U9") (pin "20") (pinfunction "GPIO10_20") (pintype "unspecified"))
    )
    (net (code "98") (name "unconnected-(U9-GPIO12-Pad6)") (class "Default")
      (node (ref "U9") (pin "6") (pinfunction "GPIO12_6") (pintype "unspecified"))
    )
    (net (code "99") (name "unconnected-(U9-GPIO13-Pad7)") (class "Default")
      (node (ref "U9") (pin "7") (pinfunction "GPIO13_7") (pintype "unspecified"))
    )
    (net (code "100") (name "unconnected-(U9-GPIO14-Pad5)") (class "Default")
      (node (ref "U9") (pin "5") (pinfunction "GPIO14_5") (pintype "unspecified"))
    )
    (net (code "101") (name "unconnected-(U9-GPIO16-Pad4)") (class "Default")
      (node (ref "U9") (pin "4") (pinfunction "GPIO16_4") (pintype "unspecified"))
    )
    (net (code "102") (name "unconnected-(U9-MISO-Pad18)") (class "Default")
      (node (ref "U9") (pin "18") (pinfunction "MISO_18") (pintype "unspecified"))
    )
    (net (code "103") (name "unconnected-(U9-MOSI-Pad21)") (class "Default")
      (node (ref "U9") (pin "21") (pinfunction "MOSI_21") (pintype "unspecified"))
    )
    (net (code "104") (name "unconnected-(U9-RXD0-Pad15)") (class "Default")
      (node (ref "U9") (pin "15") (pinfunction "RXD0_15") (pintype "unspecified"))
    )
    (net (code "105") (name "unconnected-(U9-SCLK-Pad22)") (class "Default")
      (node (ref "U9") (pin "22") (pinfunction "SCLK_22") (pintype "unspecified"))
    )
    (net (code "106") (name "unconnected-(U9-TXD0-Pad16)") (class "Default")
      (node (ref "U9") (pin "16") (pinfunction "TXD0_16") (pintype "unspecified"))
    )
  )
)
